# BeagleBoneBlackPowerMeterCap.net
KiCad netlist of a schematic drawn in Altium Designer
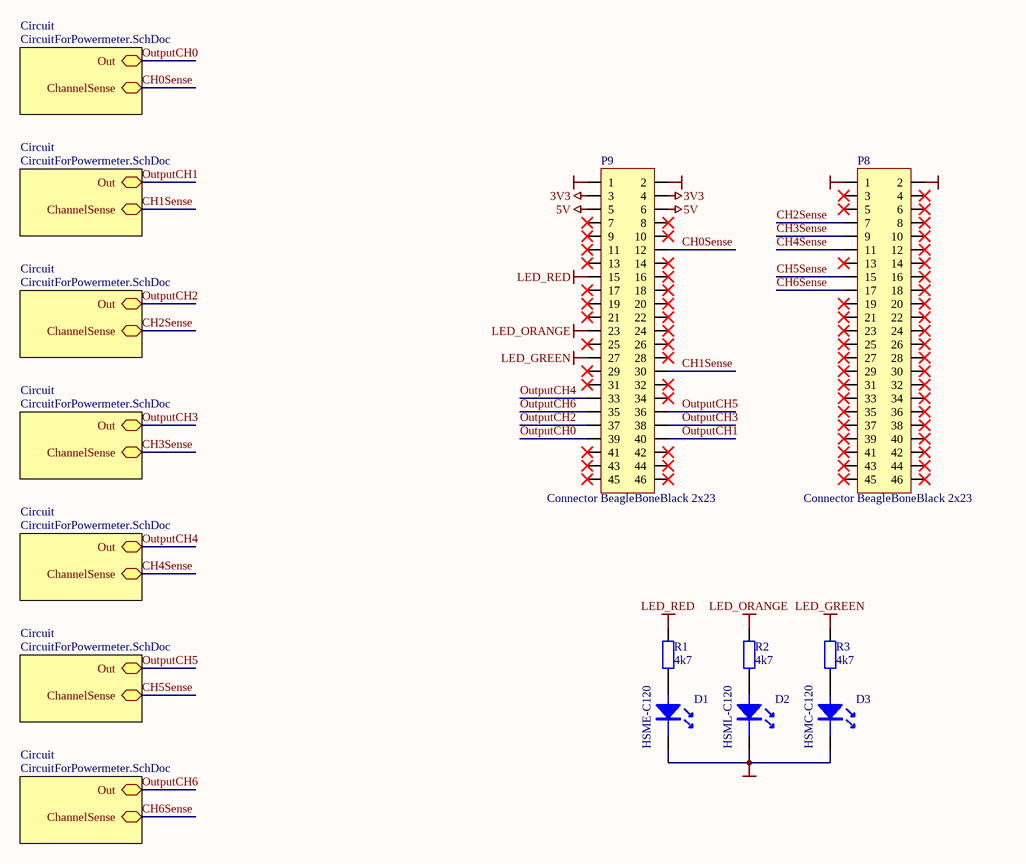
[diagram p0: BeagleBoneBlackPowerMeterCap.SchDoc]

(export (version "E")
  (design (tool "Eeschema 10.0.6"))
  (components
    (comp (ref "D1")
      (value "HSME-C120")
      (footprint "AVAGO_HSMx-C120")
      (description "LED right angle green")
      (libsource (lib "epc_cmd_default") (part "HSME-C120"))
    )
    (comp (ref "D2")
      (value "HSML-C120")
      (footprint "AVAGO_HSMx-C120")
      (description "LED right angle orange")
      (libsource (lib "epc_cmd_default") (part "HSML-C120"))
    )
    (comp (ref "D3")
      (value "HSMC-C120")
      (footprint "AVAGO_HSMx-C120")
      (description "LED right angle red")
      (libsource (lib "epc_cmd_default") (part "HSMC-C120"))
    )
    (comp (ref "P8")
      (value "Connector BeagleBoneBlack 2x23")
      (footprint "Connector_BeagleBoneBlack_2x23")
      (description "23pin dual row header")
      (libsource (lib "electro") (part "J_Connector_BeagleBoneBlack_2x23"))
    )
    (comp (ref "P9")
      (value "Connector BeagleBoneBlack 2x23")
      (footprint "Connector_BeagleBoneBlack_2x23")
      (description "23pin dual row header")
      (libsource (lib "electro") (part "J_Connector_BeagleBoneBlack_2x23"))
    )
    (comp (ref "R1")
      (value "4k7")
      (footprint "0805_R")
      (description "Resistor")
      (libsource (lib "passive") (part "R"))
    )
    (comp (ref "R2")
      (value "4k7")
      (footprint "0805_R")
      (description "Resistor")
      (libsource (lib "passive") (part "R"))
    )
    (comp (ref "R3")
      (value "4k7")
      (footprint "0805_R")
      (description "Resistor")
      (libsource (lib "passive") (part "R"))
    )
  )
  (nets
    (net (code "1") (name "/CH0Sense") (class "Default")
      (node (ref "P9") (pin "12") (pinfunction "12_12") (pintype "passive"))
    )
    (net (code "2") (name "/CH1Sense") (class "Default")
      (node (ref "P9") (pin "30") (pinfunction "30_30") (pintype "passive"))
    )
    (net (code "3") (name "/CH2Sense") (class "Default")
      (node (ref "P8") (pin "7") (pinfunction "7_7") (pintype "passive"))
    )
    (net (code "4") (name "/CH3Sense") (class "Default")
      (node (ref "P8") (pin "9") (pinfunction "9_9") (pintype "passive"))
    )
    (net (code "5") (name "/CH4Sense") (class "Default")
      (node (ref "P8") (pin "11") (pinfunction "11_11") (pintype "passive"))
    )
    (net (code "6") (name "/CH5Sense") (class "Default")
      (node (ref "P8") (pin "15") (pinfunction "15_15") (pintype "passive"))
    )
    (net (code "7") (name "/CH6Sense") (class "Default")
      (node (ref "P8") (pin "17") (pinfunction "17_17") (pintype "passive"))
    )
    (net (code "8") (name "/OutputCH0") (class "Default")
      (node (ref "P9") (pin "39") (pinfunction "39_39") (pintype "passive"))
    )
    (net (code "9") (name "/OutputCH1") (class "Default")
      (node (ref "P9") (pin "40") (pinfunction "40_40") (pintype "passive"))
    )
    (net (code "10") (name "/OutputCH2") (class "Default")
      (node (ref "P9") (pin "37") (pinfunction "37_37") (pintype "passive"))
    )
    (net (code "11") (name "/OutputCH3") (class "Default")
      (node (ref "P9") (pin "38") (pinfunction "38_38") (pintype "passive"))
    )
    (net (code "12") (name "/OutputCH4") (class "Default")
      (node (ref "P9") (pin "33") (pinfunction "33_33") (pintype "passive"))
    )
    (net (code "13") (name "/OutputCH5") (class "Default")
      (node (ref "P9") (pin "36") (pinfunction "36_36") (pintype "passive"))
    )
    (net (code "14") (name "/OutputCH6") (class "Default")
      (node (ref "P9") (pin "35") (pinfunction "35_35") (pintype "passive"))
    )
    (net (code "15") (name "3V3") (class "Default")
      (node (ref "P9") (pin "3") (pinfunction "3_3") (pintype "passive"))
      (node (ref "P9") (pin "4") (pinfunction "4_4") (pintype "passive"))
    )
    (net (code "16") (name "5V") (class "Default")
      (node (ref "P9") (pin "5") (pinfunction "5_5") (pintype "passive"))
      (node (ref "P9") (pin "6") (pinfunction "6_6") (pintype "passive"))
    )
    (net (code "17") (name "<NO NET>") (class "Default")
      (node (ref "D1") (pin "C") (pinfunction "C_C") (pintype "passive"))
      (node (ref "D2") (pin "C") (pinfunction "C_C") (pintype "passive"))
      (node (ref "D3") (pin "C") (pinfunction "C_C") (pintype "passive"))
      (node (ref "P8") (pin "1") (pinfunction "1_1") (pintype "passive"))
      (node (ref "P8") (pin "2") (pinfunction "2_2") (pintype "passive"))
      (node (ref "P9") (pin "1") (pinfunction "1_1") (pintype "passive"))
      (node (ref "P9") (pin "2") (pinfunction "2_2") (pintype "passive"))
    )
    (net (code "18") (name "LED_GREEN") (class "Default")
      (node (ref "P9") (pin "27") (pinfunction "27_27") (pintype "passive"))
      (node (ref "R3") (pin "2") (pinfunction "2_2") (pintype "passive"))
    )
    (net (code "19") (name "LED_ORANGE") (class "Default")
      (node (ref "P9") (pin "23") (pinfunction "23_23") (pintype "passive"))
      (node (ref "R2") (pin "2") (pinfunction "2_2") (pintype "passive"))
    )
    (net (code "20") (name "LED_RED") (class "Default")
      (node (ref "P9") (pin "15") (pinfunction "15_15") (pintype "passive"))
      (node (ref "R1") (pin "2") (pinfunction "2_2") (pintype "passive"))
    )
    (net (code "21") (name "Net-(D1-PadA)") (class "Default")
      (node (ref "D1") (pin "A") (pinfunction "A_A") (pintype "passive"))
      (node (ref "R1") (pin "1") (pinfunction "1_1") (pintype "passive"))
    )
    (net (code "22") (name "Net-(D2-PadA)") (class "Default")
      (node (ref "D2") (pin "A") (pinfunction "A_A") (pintype "passive"))
      (node (ref "R2") (pin "1") (pinfunction "1_1") (pintype "passive"))
    )
    (net (code "23") (name "Net-(D3-PadA)") (class "Default")
      (node (ref "D3") (pin "A") (pinfunction "A_A") (pintype "passive"))
      (node (ref "R3") (pin "1") (pinfunction "1_1") (pintype "passive"))
    )
    (net (code "24") (name "unconnected-(P8-Pad3)") (class "Default")
      (node (ref "P8") (pin "3") (pinfunction "3_3") (pintype "passive+no_connect"))
    )
    (net (code "25") (name "unconnected-(P8-Pad4)") (class "Default")
      (node (ref "P8") (pin "4") (pinfunction "4_4") (pintype "passive+no_connect"))
    )
    (net (code "26") (name "unconnected-(P8-Pad5)") (class "Default")
      (node (ref "P8") (pin "5") (pinfunction "5_5") (pintype "passive+no_connect"))
    )
    (net (code "27") (name "unconnected-(P8-Pad6)") (class "Default")
      (node (ref "P8") (pin "6") (pinfunction "6_6") (pintype "passive+no_connect"))
    )
    (net (code "28") (name "unconnected-(P8-Pad8)") (class "Default")
      (node (ref "P8") (pin "8") (pinfunction "8_8") (pintype "passive+no_connect"))
    )
    (net (code "29") (name "unconnected-(P8-Pad10)") (class "Default")
      (node (ref "P8") (pin "10") (pinfunction "10_10") (pintype "passive+no_connect"))
    )
    (net (code "30") (name "unconnected-(P8-Pad12)") (class "Default")
      (node (ref "P8") (pin "12") (pinfunction "12_12") (pintype "passive+no_connect"))
    )
    (net (code "31") (name "unconnected-(P8-Pad13)") (class "Default")
      (node (ref "P8") (pin "13") (pinfunction "13_13") (pintype "passive+no_connect"))
    )
    (net (code "32") (name "unconnected-(P8-Pad14)") (class "Default")
      (node (ref "P8") (pin "14") (pinfunction "14_14") (pintype "passive+no_connect"))
    )
    (net (code "33") (name "unconnected-(P8-Pad16)") (class "Default")
      (node (ref "P8") (pin "16") (pinfunction "16_16") (pintype "passive+no_connect"))
    )
    (net (code "34") (name "unconnected-(P8-Pad18)") (class "Default")
      (node (ref "P8") (pin "18") (pinfunction "18_18") (pintype "passive+no_connect"))
    )
    (net (code "35") (name "unconnected-(P8-Pad19)") (class "Default")
      (node (ref "P8") (pin "19") (pinfunction "19_19") (pintype "passive+no_connect"))
    )
    (net (code "36") (name "unconnected-(P8-Pad20)") (class "Default")
      (node (ref "P8") (pin "20") (pinfunction "20_20") (pintype "passive+no_connect"))
    )
    (net (code "37") (name "unconnected-(P8-Pad21)") (class "Default")
      (node (ref "P8") (pin "21") (pinfunction "21_21") (pintype "passive+no_connect"))
    )
    (net (code "38") (name "unconnected-(P8-Pad22)") (class "Default")
      (node (ref "P8") (pin "22") (pinfunction "22_22") (pintype "passive+no_connect"))
    )
    (net (code "39") (name "unconnected-(P8-Pad23)") (class "Default")
      (node (ref "P8") (pin "23") (pinfunction "23_23") (pintype "passive+no_connect"))
    )
    (net (code "40") (name "unconnected-(P8-Pad24)") (class "Default")
      (node (ref "P8") (pin "24") (pinfunction "24_24") (pintype "passive+no_connect"))
    )
    (net (code "41") (name "unconnected-(P8-Pad25)") (class "Default")
      (node (ref "P8") (pin "25") (pinfunction "25_25") (pintype "passive+no_connect"))
    )
    (net (code "42") (name "unconnected-(P8-Pad26)") (class "Default")
      (node (ref "P8") (pin "26") (pinfunction "26_26") (pintype "passive+no_connect"))
    )
    (net (code "43") (name "unconnected-(P8-Pad27)") (class "Default")
      (node (ref "P8") (pin "27") (pinfunction "27_27") (pintype "passive+no_connect"))
    )
    (net (code "44") (name "unconnected-(P8-Pad28)") (class "Default")
      (node (ref "P8") (pin "28") (pinfunction "28_28") (pintype "passive+no_connect"))
    )
    (net (code "45") (name "unconnected-(P8-Pad29)") (class "Default")
      (node (ref "P8") (pin "29") (pinfunction "29_29") (pintype "passive+no_connect"))
    )
    (net (code "46") (name "unconnected-(P8-Pad30)") (class "Default")
      (node (ref "P8") (pin "30") (pinfunction "30_30") (pintype "passive+no_connect"))
    )
    (net (code "47") (name "unconnected-(P8-Pad31)") (class "Default")
      (node (ref "P8") (pin "31") (pinfunction "31_31") (pintype "passive+no_connect"))
    )
    (net (code "48") (name "unconnected-(P8-Pad32)") (class "Default")
      (node (ref "P8") (pin "32") (pinfunction "32_32") (pintype "passive+no_connect"))
    )
    (net (code "49") (name "unconnected-(P8-Pad33)") (class "Default")
      (node (ref "P8") (pin "33") (pinfunction "33_33") (pintype "passive+no_connect"))
    )
    (net (code "50") (name "unconnected-(P8-Pad34)") (class "Default")
      (node (ref "P8") (pin "34") (pinfunction "34_34") (pintype "passive+no_connect"))
    )
    (net (code "51") (name "unconnected-(P8-Pad35)") (class "Default")
      (node (ref "P8") (pin "35") (pinfunction "35_35") (pintype "passive+no_connect"))
    )
    (net (code "52") (name "unconnected-(P8-Pad36)") (class "Default")
      (node (ref "P8") (pin "36") (pinfunction "36_36") (pintype "passive+no_connect"))
    )
    (net (code "53") (name "unconnected-(P8-Pad37)") (class "Default")
      (node (ref "P8") (pin "37") (pinfunction "37_37") (pintype "passive+no_connect"))
    )
    (net (code "54") (name "unconnected-(P8-Pad38)") (class "Default")
      (node (ref "P8") (pin "38") (pinfunction "38_38") (pintype "passive+no_connect"))
    )
    (net (code "55") (name "unconnected-(P8-Pad39)") (class "Default")
      (node (ref "P8") (pin "39") (pinfunction "39_39") (pintype "passive+no_connect"))
    )
    (net (code "56") (name "unconnected-(P8-Pad40)") (class "Default")
      (node (ref "P8") (pin "40") (pinfunction "40_40") (pintype "passive+no_connect"))
    )
    (net (code "57") (name "unconnected-(P8-Pad41)") (class "Default")
      (node (ref "P8") (pin "41") (pinfunction "41_41") (pintype "passive+no_connect"))
    )
    (net (code "58") (name "unconnected-(P8-Pad42)") (class "Default")
      (node (ref "P8") (pin "42") (pinfunction "42_42") (pintype "passive+no_connect"))
    )
    (net (code "59") (name "unconnected-(P8-Pad43)") (class "Default")
      (node (ref "P8") (pin "43") (pinfunction "43_43") (pintype "passive+no_connect"))
    )
    (net (code "60") (name "unconnected-(P8-Pad44)") (class "Default")
      (node (ref "P8") (pin "44") (pinfunction "44_44") (pintype "passive+no_connect"))
    )
    (net (code "61") (name "unconnected-(P8-Pad45)") (class "Default")
      (node (ref "P8") (pin "45") (pinfunction "45_45") (pintype "passive+no_connect"))
    )
    (net (code "62") (name "unconnected-(P8-Pad46)") (class "Default")
      (node (ref "P8") (pin "46") (pinfunction "46_46") (pintype "passive+no_connect"))
    )
    (net (code "63") (name "unconnected-(P9-Pad7)") (class "Default")
      (node (ref "P9") (pin "7") (pinfunction "7_7") (pintype "passive+no_connect"))
    )
    (net (code "64") (name "unconnected-(P9-Pad8)") (class "Default")
      (node (ref "P9") (pin "8") (pinfunction "8_8") (pintype "passive+no_connect"))
    )
    (net (code "65") (name "unconnected-(P9-Pad9)") (class "Default")
      (node (ref "P9") (pin "9") (pinfunction "9_9") (pintype "passive+no_connect"))
    )
    (net (code "66") (name "unconnected-(P9-Pad10)") (class "Default")
      (node (ref "P9") (pin "10") (pinfunction "10_10") (pintype "passive+no_connect"))
    )
    (net (code "67") (name "unconnected-(P9-Pad11)") (class "Default")
      (node (ref "P9") (pin "11") (pinfunction "11_11") (pintype "passive+no_connect"))
    )
    (net (code "68") (name "unconnected-(P9-Pad13)") (class "Default")
      (node (ref "P9") (pin "13") (pinfunction "13_13") (pintype "passive+no_connect"))
    )
    (net (code "69") (name "unconnected-(P9-Pad14)") (class "Default")
      (node (ref "P9") (pin "14") (pinfunction "14_14") (pintype "passive+no_connect"))
    )
    (net (code "70") (name "unconnected-(P9-Pad16)") (class "Default")
      (node (ref "P9") (pin "16") (pinfunction "16_16") (pintype "passive+no_connect"))
    )
    (net (code "71") (name "unconnected-(P9-Pad17)") (class "Default")
      (node (ref "P9") (pin "17") (pinfunction "17_17") (pintype "passive+no_connect"))
    )
    (net (code "72") (name "unconnected-(P9-Pad18)") (class "Default")
      (node (ref "P9") (pin "18") (pinfunction "18_18") (pintype "passive+no_connect"))
    )
    (net (code "73") (name "unconnected-(P9-Pad19)") (class "Default")
      (node (ref "P9") (pin "19") (pinfunction "19_19") (pintype "passive+no_connect"))
    )
    (net (code "74") (name "unconnected-(P9-Pad20)") (class "Default")
      (node (ref "P9") (pin "20") (pinfunction "20_20") (pintype "passive+no_connect"))
    )
    (net (code "75") (name "unconnected-(P9-Pad21)") (class "Default")
      (node (ref "P9") (pin "21") (pinfunction "21_21") (pintype "passive+no_connect"))
    )
    (net (code "76") (name "unconnected-(P9-Pad22)") (class "Default")
      (node (ref "P9") (pin "22") (pinfunction "22_22") (pintype "passive+no_connect"))
    )
    (net (code "77") (name "unconnected-(P9-Pad24)") (class "Default")
      (node (ref "P9") (pin "24") (pinfunction "24_24") (pintype "passive+no_connect"))
    )
    (net (code "78") (name "unconnected-(P9-Pad25)") (class "Default")
      (node (ref "P9") (pin "25") (pinfunction "25_25") (pintype "passive+no_connect"))
    )
    (net (code "79") (name "unconnected-(P9-Pad26)") (class "Default")
      (node (ref "P9") (pin "26") (pinfunction "26_26") (pintype "passive+no_connect"))
    )
    (net (code "80") (name "unconnected-(P9-Pad28)") (class "Default")
      (node (ref "P9") (pin "28") (pinfunction "28_28") (pintype "passive+no_connect"))
    )
    (net (code "81") (name "unconnected-(P9-Pad29)") (class "Default")
      (node (ref "P9") (pin "29") (pinfunction "29_29") (pintype "passive+no_connect"))
    )
    (net (code "82") (name "unconnected-(P9-Pad31)") (class "Default")
      (node (ref "P9") (pin "31") (pinfunction "31_31") (pintype "passive+no_connect"))
    )
    (net (code "83") (name "unconnected-(P9-Pad32)") (class "Default")
      (node (ref "P9") (pin "32") (pinfunction "32_32") (pintype "passive+no_connect"))
    )
    (net (code "84") (name "unconnected-(P9-Pad34)") (class "Default")
      (node (ref "P9") (pin "34") (pinfunction "34_34") (pintype "passive+no_connect"))
    )
    (net (code "85") (name "unconnected-(P9-Pad41)") (class "Default")
      (node (ref "P9") (pin "41") (pinfunction "41_41") (pintype "passive+no_connect"))
    )
    (net (code "86") (name "unconnected-(P9-Pad42)") (class "Default")
      (node (ref "P9") (pin "42") (pinfunction "42_42") (pintype "passive+no_connect"))
    )
    (net (code "87") (name "unconnected-(P9-Pad43)") (class "Default")
      (node (ref "P9") (pin "43") (pinfunction "43_43") (pintype "passive+no_connect"))
    )
    (net (code "88") (name "unconnected-(P9-Pad44)") (class "Default")
      (node (ref "P9") (pin "44") (pinfunction "44_44") (pintype "passive+no_connect"))
    )
    (net (code "89") (name "unconnected-(P9-Pad45)") (class "Default")
      (node (ref "P9") (pin "45") (pinfunction "45_45") (pintype "passive+no_connect"))
    )
    (net (code "90") (name "unconnected-(P9-Pad46)") (class "Default")
      (node (ref "P9") (pin "46") (pinfunction "46_46") (pintype "passive+no_connect"))
    )
  )
)
